# 9_-MODEM_POWER.net
KiCad netlist of a schematic drawn in Altium Designer
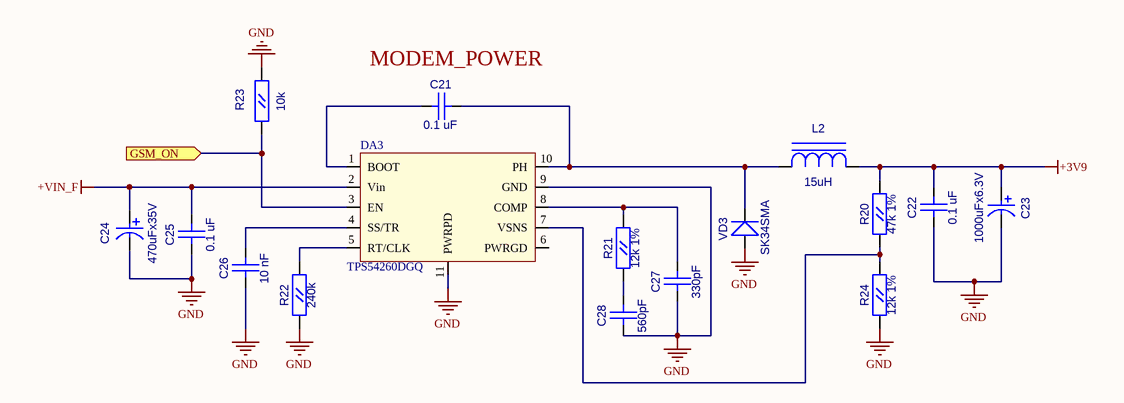
[diagram p0: [9]-MODEM_POWER.SchDoc]

(export (version "E")
  (design (tool "Eeschema 10.0.6"))
  (components
    (comp (ref "C21")
      (value "0.1 uF")
      (footprint "CC0603")
      (description "CC0603")
      (libsource (lib "gprs_modem_2") (part "CC0603"))
    )
    (comp (ref "C22")
      (value "0.1 uF")
      (footprint "CC0603")
      (description "CC0603")
      (libsource (lib "gprs_modem_2") (part "CC0603"))
    )
    (comp (ref "C23")
      (value "1000uFx6.3V")
      (footprint "CAP_8x14_R")
      (description "Radial capacitor")
      (libsource (lib "fizik_lib (1)") (part "CAP_8mm"))
    )
    (comp (ref "C24")
      (value "470uFx35V")
      (footprint "CC16X10_CAP0.5(1)(Primary)")
      (description "CAP0.5(1)")
      (libsource (lib "gprs_modem_2") (part "CAP0.5(1)"))
    )
    (comp (ref "C25")
      (value "0.1 uF")
      (footprint "CC0603")
      (description "CC0603")
      (libsource (lib "gprs_modem_2") (part "CC0603"))
    )
    (comp (ref "C26")
      (value "10 nF")
      (footprint "CC0603")
      (description "CC0603")
      (libsource (lib "gprs_modem_2") (part "CC0603"))
    )
    (comp (ref "C27")
      (value "330pF")
      (footprint "CC0603")
      (description "CC0603")
      (libsource (lib "gprs_modem_2") (part "CC0603"))
    )
    (comp (ref "C28")
      (value "560pF")
      (footprint "CC0603")
      (description "CC0603")
      (libsource (lib "gprs_modem_2") (part "CC0603"))
    )
    (comp (ref "DA3")
      (value "TPS54260DGQ")
      (footprint "S-PDSO-G10")
      (libsource (lib "gprs_modem_2") (part "TPS54260DGQ"))
    )
    (comp (ref "L2")
      (value "15uH")
      (footprint "SDR0805")
      (description "SDR0805")
      (libsource (lib "gprs_modem_2") (part "SDR0805"))
    )
    (comp (ref "R20")
      (value "47k 1%")
      (footprint "RC0603")
      (description "RC0603")
      (libsource (lib "gprs_modem_2") (part "RC0603"))
    )
    (comp (ref "R21")
      (value "12k 1%")
      (footprint "RC0603")
      (description "RC0603")
      (libsource (lib "gprs_modem_2") (part "RC0603"))
    )
    (comp (ref "R22")
      (value "240k")
      (footprint "RC0603")
      (description "RC0603")
      (libsource (lib "gprs_modem_2") (part "RC0603"))
    )
    (comp (ref "R23")
      (value "10k")
      (footprint "RC0603")
      (description "RC0603")
      (libsource (lib "gprs_modem_2") (part "RC0603"))
    )
    (comp (ref "R24")
      (value "12k 1%")
      (footprint "RC0603")
      (description "RC0603")
      (libsource (lib "gprs_modem_2") (part "RC0603"))
    )
    (comp (ref "VD3")
      (value "SK34SMA")
      (footprint "SMA")
      (description "Schottky Rectifier")
      (libsource (lib "gprs_modem") (part "SK34SMA"))
    )
  )
  (nets
    (net (code "1") (name "+3V9") (class "Default")
      (node (ref "C22") (pin "1") (pinfunction "A_1") (pintype "passive"))
      (node (ref "C23") (pin "1") (pintype "passive"))
      (node (ref "L2") (pin "2") (pinfunction "A_2") (pintype "passive"))
      (node (ref "R20") (pin "2") (pinfunction "B_2") (pintype "passive"))
    )
    (net (code "2") (name "+VIN_F") (class "Default")
      (node (ref "C24") (pin "2") (pintype "passive"))
      (node (ref "C25") (pin "1") (pinfunction "A_1") (pintype "passive"))
      (node (ref "DA3") (pin "2") (pinfunction "Vin_2") (pintype "passive"))
    )
    (net (code "3") (name "/GSM_ON") (class "Default")
      (node (ref "DA3") (pin "3") (pinfunction "EN_3") (pintype "passive"))
      (node (ref "R23") (pin "1") (pinfunction "A_1") (pintype "passive"))
    )
    (net (code "4") (name "GND") (class "Default")
      (node (ref "C22") (pin "2") (pinfunction "B_2") (pintype "passive"))
      (node (ref "C23") (pin "2") (pintype "passive"))
      (node (ref "C24") (pin "1") (pintype "passive"))
      (node (ref "C25") (pin "2") (pinfunction "B_2") (pintype "passive"))
      (node (ref "C26") (pin "2") (pinfunction "B_2") (pintype "passive"))
      (node (ref "C27") (pin "2") (pinfunction "B_2") (pintype "passive"))
      (node (ref "C28") (pin "2") (pinfunction "B_2") (pintype "passive"))
      (node (ref "DA3") (pin "11") (pinfunction "PWRPD_11") (pintype "passive"))
      (node (ref "DA3") (pin "9") (pinfunction "GND_9") (pintype "passive"))
      (node (ref "R22") (pin "1") (pinfunction "A_1") (pintype "passive"))
      (node (ref "R23") (pin "2") (pinfunction "B_2") (pintype "passive"))
      (node (ref "R24") (pin "1") (pinfunction "A_1") (pintype "passive"))
      (node (ref "VD3") (pin "1") (pinfunction "A_1") (pintype "passive"))
    )
    (net (code "5") (name "Net-(C21-A)") (class "Default")
      (node (ref "C21") (pin "1") (pinfunction "A_1") (pintype "passive"))
      (node (ref "DA3") (pin "10") (pinfunction "PH_10") (pintype "passive"))
      (node (ref "L2") (pin "1") (pinfunction "C_1") (pintype "passive"))
      (node (ref "VD3") (pin "2") (pinfunction "K_2") (pintype "passive"))
    )
    (net (code "6") (name "Net-(C21-B)") (class "Default")
      (node (ref "C21") (pin "2") (pinfunction "B_2") (pintype "passive"))
      (node (ref "DA3") (pin "1") (pinfunction "BOOT_1") (pintype "passive"))
    )
    (net (code "7") (name "Net-(C26-A)") (class "Default")
      (node (ref "C26") (pin "1") (pinfunction "A_1") (pintype "passive"))
      (node (ref "DA3") (pin "4") (pinfunction "SS/TR_4") (pintype "passive"))
    )
    (net (code "8") (name "Net-(C27-A)") (class "Default")
      (node (ref "C27") (pin "1") (pinfunction "A_1") (pintype "passive"))
      (node (ref "DA3") (pin "8") (pinfunction "COMP_8") (pintype "passive"))
      (node (ref "R21") (pin "2") (pinfunction "B_2") (pintype "passive"))
    )
    (net (code "9") (name "Net-(C28-A)") (class "Default")
      (node (ref "C28") (pin "1") (pinfunction "A_1") (pintype "passive"))
      (node (ref "R21") (pin "1") (pinfunction "A_1") (pintype "passive"))
    )
    (net (code "10") (name "Net-(DA3-RT{slash}CLK)") (class "Default")
      (node (ref "DA3") (pin "5") (pinfunction "RT/CLK_5") (pintype "passive"))
      (node (ref "R22") (pin "2") (pinfunction "B_2") (pintype "passive"))
    )
    (net (code "11") (name "Net-(DA3-VSNS)") (class "Default")
      (node (ref "DA3") (pin "7") (pinfunction "VSNS_7") (pintype "passive"))
      (node (ref "R20") (pin "1") (pinfunction "A_1") (pintype "passive"))
      (node (ref "R24") (pin "2") (pinfunction "B_2") (pintype "passive"))
    )
    (net (code "12") (name "unconnected-(DA3-PWRGD-Pad6)") (class "Default")
      (node (ref "DA3") (pin "6") (pinfunction "PWRGD_6") (pintype "passive"))
    )
  )
)
